# Pi-XMEGA.net
KiCad netlist of a schematic drawn in EAGLE
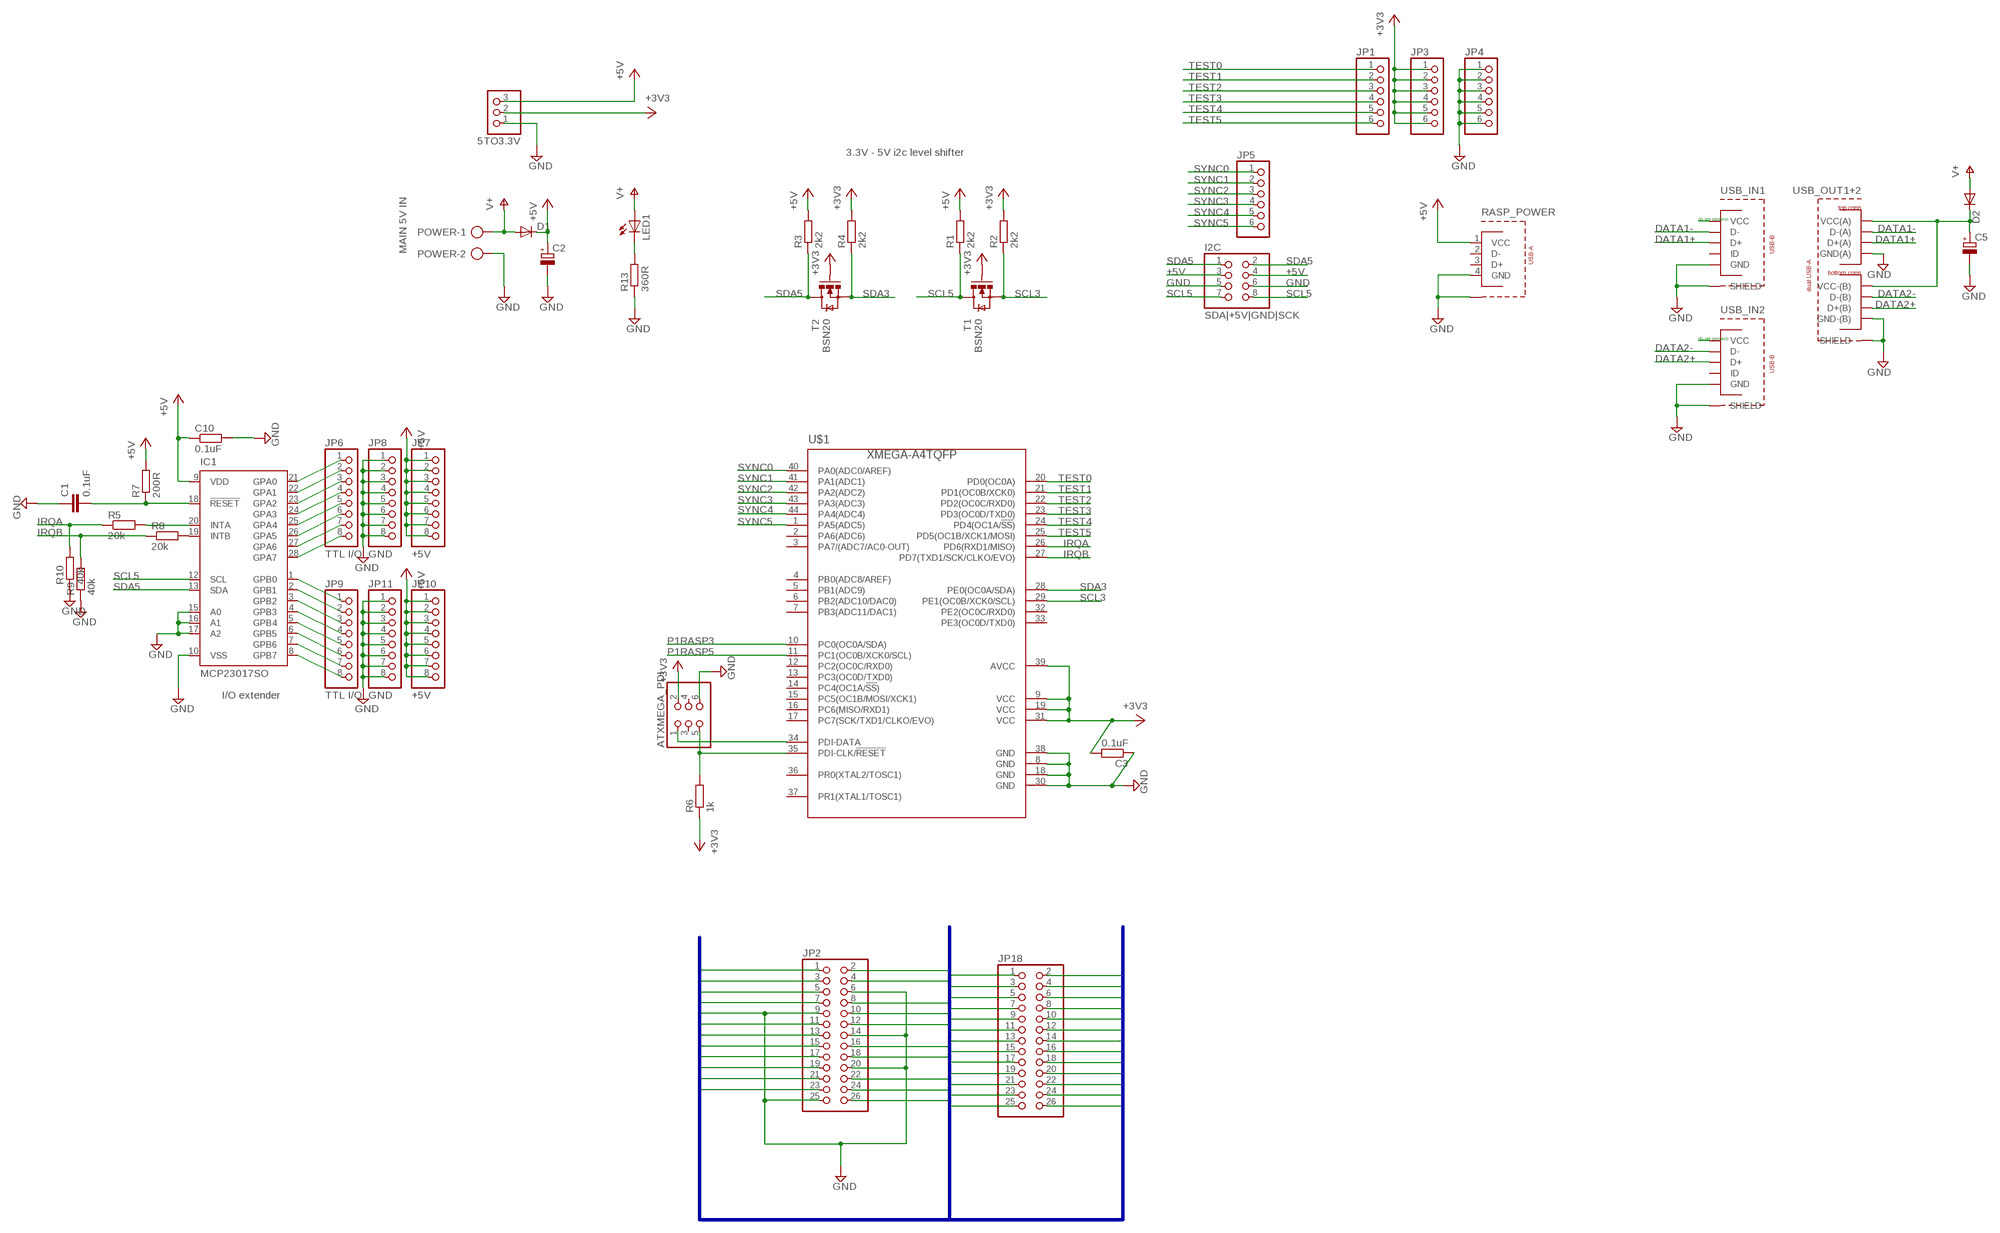
[diagram p0: schematic, sheet 1]

(export (version "E")
  (design (tool "Eeschema 10.0.6"))
  (components
    (comp (ref "5TO3.3V")
      (value "PINHD-1X3")
      (footprint "eagle-import:1X03")
      (libsource (lib "eagle-import") (part "PINHD-1X3"))
    )
    (comp (ref "ATXMEGA_PDI")
      (value "PINHD-2X03_2.54")
      (footprint "eagle-import:2X03")
      (libsource (lib "eagle-import") (part "PINHD-2X03_2.54"))
    )
    (comp (ref "C1")
      (value "0.1uF")
      (footprint "eagle-import:0805BIG")
      (libsource (lib "eagle-import") (part "CAPACITORC-0805BIG"))
    )
    (comp (ref "C2")
      (value "CPOL-EUE5-8.5")
      (footprint "eagle-import:E5-8,5")
      (libsource (lib "eagle-import") (part "CPOL-EUE5-8.5"))
    )
    (comp (ref "C3")
      (value "0.1uF")
      (footprint "eagle-import:0805BIG")
      (libsource (lib "eagle-import") (part "RESISTORR-0805BIG"))
    )
    (comp (ref "C5")
      (value "CPOL-EUE5-8.5")
      (footprint "eagle-import:E5-8,5")
      (libsource (lib "eagle-import") (part "CPOL-EUE5-8.5"))
    )
    (comp (ref "C10")
      (value "0.1uF")
      (footprint "eagle-import:0805BIG")
      (libsource (lib "eagle-import") (part "RESISTORR-0805BIG"))
    )
    (comp (ref "D1")
      (value "DIODE-C1702-05")
      (footprint "eagle-import:C1702-05")
      (libsource (lib "eagle-import") (part "DIODE-C1702-05"))
    )
    (comp (ref "D2")
      (value "DIODE-C1702-05")
      (footprint "eagle-import:C1702-05")
      (libsource (lib "eagle-import") (part "DIODE-C1702-05"))
    )
    (comp (ref "I2C")
      (value "SDA|+5V|GND|SCK")
      (footprint "eagle-import:2X04")
      (libsource (lib "eagle-import") (part "PINHD-2X04_2.54"))
    )
    (comp (ref "IC1")
      (value "MCP23017SO")
      (footprint "eagle-import:SO28W")
      (fields (field (name "MF") "MICROCHIP") (field (name "MPN") "MCP23017-E/SO"))
      (libsource (lib "eagle-import") (part "MCP23017SO"))
    )
    (comp (ref "JP1")
      (value "PINHD-1X06_2.54-S")
      (footprint "eagle-import:1X06-S")
      (libsource (lib "eagle-import") (part "PINHD-1X06_2.54-S"))
    )
    (comp (ref "JP2")
      (value "PINHD-2X13_2.54")
      (footprint "eagle-import:2X13")
      (libsource (lib "eagle-import") (part "PINHD-2X13_2.54"))
    )
    (comp (ref "JP3")
      (value "PINHD-1X06_2.54-S")
      (footprint "eagle-import:1X06-S")
      (libsource (lib "eagle-import") (part "PINHD-1X06_2.54-S"))
    )
    (comp (ref "JP4")
      (value "PINHD-1X06_2.54-S")
      (footprint "eagle-import:1X06-S")
      (libsource (lib "eagle-import") (part "PINHD-1X06_2.54-S"))
    )
    (comp (ref "JP5")
      (value "PINHD-1X06_2.54-S")
      (footprint "eagle-import:1X06-S")
      (libsource (lib "eagle-import") (part "PINHD-1X06_2.54-S"))
    )
    (comp (ref "JP6")
      (value "TTL I/O")
      (footprint "eagle-import:1X08-S")
      (libsource (lib "eagle-import") (part "PINHD-1X08_2.54-S"))
    )
    (comp (ref "JP7")
      (value "+5V")
      (footprint "eagle-import:1X08-S")
      (libsource (lib "eagle-import") (part "PINHD-1X08_2.54-S"))
    )
    (comp (ref "JP8")
      (value "GND")
      (footprint "eagle-import:1X08-S")
      (libsource (lib "eagle-import") (part "PINHD-1X08_2.54-S"))
    )
    (comp (ref "JP9")
      (value "TTL I/O")
      (footprint "eagle-import:1X08-S")
      (libsource (lib "eagle-import") (part "PINHD-1X08_2.54-S"))
    )
    (comp (ref "JP10")
      (value "+5V")
      (footprint "eagle-import:1X08-S")
      (libsource (lib "eagle-import") (part "PINHD-1X08_2.54-S"))
    )
    (comp (ref "JP11")
      (value "GND")
      (footprint "eagle-import:1X08-S")
      (libsource (lib "eagle-import") (part "PINHD-1X08_2.54-S"))
    )
    (comp (ref "JP18")
      (value "PINHD-2X13_2.54")
      (footprint "eagle-import:2X13")
      (libsource (lib "eagle-import") (part "PINHD-2X13_2.54"))
    )
    (comp (ref "LED1")
      (value "LED3MM")
      (footprint "eagle-import:LED3MM")
      (libsource (lib "eagle-import") (part "LED3MM"))
    )
    (comp (ref "POWER")
      (value "AK500/2")
      (footprint "eagle-import:AK500_2")
      (libsource (lib "eagle-import") (part "AK500/2"))
    )
    (comp (ref "R1")
      (value "2k2")
      (footprint "eagle-import:0805BIG")
      (libsource (lib "eagle-import") (part "RESISTORR-0805BIG"))
    )
    (comp (ref "R2")
      (value "2k2")
      (footprint "eagle-import:0805BIG")
      (libsource (lib "eagle-import") (part "RESISTORR-0805BIG"))
    )
    (comp (ref "R3")
      (value "2k2")
      (footprint "eagle-import:0805BIG")
      (libsource (lib "eagle-import") (part "MART2013_RESISTORR-0805BIG"))
    )
    (comp (ref "R4")
      (value "2k2")
      (footprint "eagle-import:0805BIG")
      (libsource (lib "eagle-import") (part "RESISTORR-0805BIG"))
    )
    (comp (ref "R5")
      (value "20k")
      (footprint "eagle-import:0805BIG")
      (libsource (lib "eagle-import") (part "RESISTORR-0805BIG"))
    )
    (comp (ref "R6")
      (value "1k")
      (footprint "eagle-import:0805BIG")
      (libsource (lib "eagle-import") (part "RESISTORR-0805BIG"))
    )
    (comp (ref "R7")
      (value "200R")
      (footprint "eagle-import:0805BIG")
      (libsource (lib "eagle-import") (part "RESISTORR-0805BIG"))
    )
    (comp (ref "R8")
      (value "20k")
      (footprint "eagle-import:0805BIG")
      (libsource (lib "eagle-import") (part "RESISTORR-0805BIG"))
    )
    (comp (ref "R9")
      (value "40k")
      (footprint "eagle-import:0805BIG")
      (libsource (lib "eagle-import") (part "RESISTORR-0805BIG"))
    )
    (comp (ref "R10")
      (value "40k")
      (footprint "eagle-import:0805BIG")
      (libsource (lib "eagle-import") (part "RESISTORR-0805BIG"))
    )
    (comp (ref "R13")
      (value "360R")
      (footprint "eagle-import:0805BIG")
      (libsource (lib "eagle-import") (part "RESISTORR-0805BIG"))
    )
    (comp (ref "RASP_POWER")
      (value "USB-A")
      (footprint "eagle-import:USB-A")
      (libsource (lib "eagle-import") (part "USB-A"))
    )
    (comp (ref "T1")
      (value "BSN20")
      (footprint "eagle-import:SOT23")
      (libsource (lib "eagle-import") (part "BSN20"))
    )
    (comp (ref "T2")
      (value "BSN20")
      (footprint "eagle-import:SOT23")
      (libsource (lib "eagle-import") (part "BSN20"))
    )
    (comp (ref "U$1")
      (value "XMEGA-A4TQFP")
      (footprint "eagle-import:TQFP44")
      (libsource (lib "eagle-import") (part "XMEGA-A4TQFP"))
    )
    (comp (ref "USB_IN1")
      (value "USB-B-MICRO")
      (footprint "eagle-import:USB-B-MICRO")
      (libsource (lib "eagle-import") (part "USB-B-MICRO"))
    )
    (comp (ref "USB_IN2")
      (value "USB-B-MICRO")
      (footprint "eagle-import:USB-B-MICRO")
      (libsource (lib "eagle-import") (part "USB-B-MICRO"))
    )
    (comp (ref "USB_OUT1+2")
      (value "DUAL-USB-A")
      (footprint "eagle-import:DUAL-USB-A")
      (libsource (lib "eagle-import") (part "DUAL-USB-A"))
    )
  )
  (nets
    (net (code "1") (name "+3V3") (class "Default")
      (node (ref "5TO3.3V") (pin "2") (pinfunction "2_2") (pintype "passive"))
      (node (ref "ATXMEGA_PDI") (pin "2") (pinfunction "2_2") (pintype "passive"))
      (node (ref "C3") (pin "2") (pinfunction "2_2") (pintype "passive"))
      (node (ref "JP3") (pin "1") (pinfunction "1_1") (pintype "passive"))
      (node (ref "JP3") (pin "2") (pinfunction "2_2") (pintype "passive"))
      (node (ref "JP3") (pin "3") (pinfunction "3_3") (pintype "passive"))
      (node (ref "JP3") (pin "4") (pinfunction "4_4") (pintype "passive"))
      (node (ref "JP3") (pin "5") (pinfunction "5_5") (pintype "passive"))
      (node (ref "JP3") (pin "6") (pinfunction "6_6") (pintype "passive"))
      (node (ref "R2") (pin "2") (pinfunction "2_2") (pintype "passive"))
      (node (ref "R4") (pin "2") (pinfunction "2_2") (pintype "passive"))
      (node (ref "R6") (pin "1") (pinfunction "1_1") (pintype "passive"))
      (node (ref "T1") (pin "1") (pinfunction "G_1") (pintype "passive"))
      (node (ref "T2") (pin "1") (pinfunction "G_1") (pintype "passive"))
      (node (ref "U$1") (pin "19") (pinfunction "VCC_19") (pintype "power_in"))
      (node (ref "U$1") (pin "31") (pinfunction "VCC_31") (pintype "power_in"))
      (node (ref "U$1") (pin "39") (pinfunction "AVCC_39") (pintype "power_in"))
      (node (ref "U$1") (pin "9") (pinfunction "VCC_9") (pintype "power_in"))
    )
    (net (code "2") (name "+5V") (class "Default")
      (node (ref "5TO3.3V") (pin "3") (pinfunction "3_3") (pintype "passive"))
      (node (ref "C10") (pin "1") (pinfunction "1_1") (pintype "passive"))
      (node (ref "C2") (pin "+") (pinfunction "+_+") (pintype "passive"))
      (node (ref "D1") (pin "C") (pinfunction "C_C") (pintype "passive"))
      (node (ref "I2C") (pin "3") (pinfunction "3_3") (pintype "passive"))
      (node (ref "I2C") (pin "4") (pinfunction "4_4") (pintype "passive"))
      (node (ref "IC1") (pin "9") (pinfunction "VDD_9") (pintype "power_in"))
      (node (ref "JP10") (pin "1") (pinfunction "1_1") (pintype "passive"))
      (node (ref "JP10") (pin "2") (pinfunction "2_2") (pintype "passive"))
      (node (ref "JP10") (pin "3") (pinfunction "3_3") (pintype "passive"))
      (node (ref "JP10") (pin "4") (pinfunction "4_4") (pintype "passive"))
      (node (ref "JP10") (pin "5") (pinfunction "5_5") (pintype "passive"))
      (node (ref "JP10") (pin "6") (pinfunction "6_6") (pintype "passive"))
      (node (ref "JP10") (pin "7") (pinfunction "7_7") (pintype "passive"))
      (node (ref "JP10") (pin "8") (pinfunction "8_8") (pintype "passive"))
      (node (ref "JP7") (pin "1") (pinfunction "1_1") (pintype "passive"))
      (node (ref "JP7") (pin "2") (pinfunction "2_2") (pintype "passive"))
      (node (ref "JP7") (pin "3") (pinfunction "3_3") (pintype "passive"))
      (node (ref "JP7") (pin "4") (pinfunction "4_4") (pintype "passive"))
      (node (ref "JP7") (pin "5") (pinfunction "5_5") (pintype "passive"))
      (node (ref "JP7") (pin "6") (pinfunction "6_6") (pintype "passive"))
      (node (ref "JP7") (pin "7") (pinfunction "7_7") (pintype "passive"))
      (node (ref "JP7") (pin "8") (pinfunction "8_8") (pintype "passive"))
      (node (ref "R1") (pin "2") (pinfunction "2_2") (pintype "passive"))
      (node (ref "R3") (pin "2") (pinfunction "2_2") (pintype "passive"))
      (node (ref "R7") (pin "2") (pinfunction "2_2") (pintype "passive"))
      (node (ref "RASP_POWER") (pin "1") (pinfunction "VCC_1") (pintype "power_in"))
    )
    (net (code "3") (name "/DATA1+") (class "Default")
      (node (ref "USB_IN1") (pin "3") (pinfunction "D+_3") (pintype "bidirectional"))
      (node (ref "USB_OUT1+2") (pin "3") (pinfunction "D+(A)_3") (pintype "bidirectional"))
    )
    (net (code "4") (name "/DATA1-") (class "Default")
      (node (ref "USB_IN1") (pin "2") (pinfunction "D-_2") (pintype "bidirectional"))
      (node (ref "USB_OUT1+2") (pin "2") (pinfunction "D-(A)_2") (pintype "bidirectional"))
    )
    (net (code "5") (name "/DATA2+") (class "Default")
      (node (ref "USB_IN2") (pin "3") (pinfunction "D+_3") (pintype "bidirectional"))
      (node (ref "USB_OUT1+2") (pin "7") (pinfunction "D+(B)_7") (pintype "bidirectional"))
    )
    (net (code "6") (name "/DATA2-") (class "Default")
      (node (ref "USB_IN2") (pin "2") (pinfunction "D-_2") (pintype "bidirectional"))
      (node (ref "USB_OUT1+2") (pin "6") (pinfunction "D-(B)_6") (pintype "bidirectional"))
    )
    (net (code "7") (name "/IRQA") (class "Default")
      (node (ref "R10") (pin "2") (pinfunction "2_2") (pintype "passive"))
      (node (ref "R5") (pin "1") (pinfunction "1_1") (pintype "passive"))
      (node (ref "U$1") (pin "26") (pinfunction "PD6(RXD1/MISO)_26") (pintype "bidirectional"))
    )
    (net (code "8") (name "/IRQB") (class "Default")
      (node (ref "R8") (pin "1") (pinfunction "1_1") (pintype "passive"))
      (node (ref "R9") (pin "2") (pinfunction "2_2") (pintype "passive"))
      (node (ref "U$1") (pin "27") (pinfunction "PD7(TXD1/SCK/CLKO/EVO)_27") (pintype "bidirectional"))
    )
    (net (code "9") (name "/P1RASP1") (class "Default")
      (node (ref "JP18") (pin "1") (pinfunction "1_1") (pintype "passive"))
      (node (ref "JP2") (pin "1") (pinfunction "1_1") (pintype "passive"))
    )
    (net (code "10") (name "/P1RASP2") (class "Default")
      (node (ref "JP18") (pin "2") (pinfunction "2_2") (pintype "passive"))
      (node (ref "JP2") (pin "2") (pinfunction "2_2") (pintype "passive"))
    )
    (net (code "11") (name "/P1RASP3") (class "Default")
      (node (ref "JP18") (pin "3") (pinfunction "3_3") (pintype "passive"))
      (node (ref "JP2") (pin "3") (pinfunction "3_3") (pintype "passive"))
      (node (ref "U$1") (pin "10") (pinfunction "PC0(OC0A/SDA)_10") (pintype "bidirectional"))
    )
    (net (code "12") (name "/P1RASP4") (class "Default")
      (node (ref "JP18") (pin "4") (pinfunction "4_4") (pintype "passive"))
      (node (ref "JP2") (pin "4") (pinfunction "4_4") (pintype "passive"))
    )
    (net (code "13") (name "/P1RASP5") (class "Default")
      (node (ref "JP18") (pin "5") (pinfunction "5_5") (pintype "passive"))
      (node (ref "JP2") (pin "5") (pinfunction "5_5") (pintype "passive"))
      (node (ref "U$1") (pin "11") (pinfunction "PC1(OC0B/XCK0/SCL)_11") (pintype "bidirectional"))
    )
    (net (code "14") (name "/P1RASP7") (class "Default")
      (node (ref "JP18") (pin "7") (pinfunction "7_7") (pintype "passive"))
      (node (ref "JP2") (pin "7") (pinfunction "7_7") (pintype "passive"))
    )
    (net (code "15") (name "/P1RASP8") (class "Default")
      (node (ref "JP18") (pin "8") (pinfunction "8_8") (pintype "passive"))
      (node (ref "JP2") (pin "8") (pinfunction "8_8") (pintype "passive"))
    )
    (net (code "16") (name "/P1RASP10") (class "Default")
      (node (ref "JP18") (pin "10") (pinfunction "10_10") (pintype "passive"))
      (node (ref "JP2") (pin "10") (pinfunction "10_10") (pintype "passive"))
    )
    (net (code "17") (name "/P1RASP11") (class "Default")
      (node (ref "JP18") (pin "11") (pinfunction "11_11") (pintype "passive"))
      (node (ref "JP2") (pin "11") (pinfunction "11_11") (pintype "passive"))
    )
    (net (code "18") (name "/P1RASP12") (class "Default")
      (node (ref "JP18") (pin "12") (pinfunction "12_12") (pintype "passive"))
      (node (ref "JP2") (pin "12") (pinfunction "12_12") (pintype "passive"))
    )
    (net (code "19") (name "/P1RASP13") (class "Default")
      (node (ref "JP18") (pin "13") (pinfunction "13_13") (pintype "passive"))
      (node (ref "JP2") (pin "13") (pinfunction "13_13") (pintype "passive"))
    )
    (net (code "20") (name "/P1RASP15") (class "Default")
      (node (ref "JP18") (pin "15") (pinfunction "15_15") (pintype "passive"))
      (node (ref "JP2") (pin "15") (pinfunction "15_15") (pintype "passive"))
    )
    (net (code "21") (name "/P1RASP16") (class "Default")
      (node (ref "JP18") (pin "16") (pinfunction "16_16") (pintype "passive"))
      (node (ref "JP2") (pin "16") (pinfunction "16_16") (pintype "passive"))
    )
    (net (code "22") (name "/P1RASP17") (class "Default")
      (node (ref "JP18") (pin "17") (pinfunction "17_17") (pintype "passive"))
      (node (ref "JP2") (pin "17") (pinfunction "17_17") (pintype "passive"))
    )
    (net (code "23") (name "/P1RASP18") (class "Default")
      (node (ref "JP18") (pin "18") (pinfunction "18_18") (pintype "passive"))
      (node (ref "JP2") (pin "18") (pinfunction "18_18") (pintype "passive"))
    )
    (net (code "24") (name "/P1RASP19") (class "Default")
      (node (ref "JP18") (pin "19") (pinfunction "19_19") (pintype "passive"))
      (node (ref "JP2") (pin "19") (pinfunction "19_19") (pintype "passive"))
    )
    (net (code "25") (name "/P1RASP21") (class "Default")
      (node (ref "JP18") (pin "21") (pinfunction "21_21") (pintype "passive"))
      (node (ref "JP2") (pin "21") (pinfunction "21_21") (pintype "passive"))
    )
    (net (code "26") (name "/P1RASP22") (class "Default")
      (node (ref "JP18") (pin "22") (pinfunction "22_22") (pintype "passive"))
      (node (ref "JP2") (pin "22") (pinfunction "22_22") (pintype "passive"))
    )
    (net (code "27") (name "/P1RASP23") (class "Default")
      (node (ref "JP18") (pin "23") (pinfunction "23_23") (pintype "passive"))
      (node (ref "JP2") (pin "23") (pinfunction "23_23") (pintype "passive"))
    )
    (net (code "28") (name "/P1RASP24") (class "Default")
      (node (ref "JP18") (pin "24") (pinfunction "24_24") (pintype "passive"))
      (node (ref "JP2") (pin "24") (pinfunction "24_24") (pintype "passive"))
    )
    (net (code "29") (name "/P1RASP26") (class "Default")
      (node (ref "JP18") (pin "26") (pinfunction "26_26") (pintype "passive"))
      (node (ref "JP2") (pin "26") (pinfunction "26_26") (pintype "passive"))
    )
    (net (code "30") (name "/SCL3") (class "Default")
      (node (ref "R2") (pin "1") (pinfunction "1_1") (pintype "passive"))
      (node (ref "T1") (pin "2") (pinfunction "S_2") (pintype "passive"))
      (node (ref "U$1") (pin "29") (pinfunction "PE1(OC0B/XCK0/SCL)_29") (pintype "bidirectional"))
    )
    (net (code "31") (name "/SCL5") (class "Default")
      (node (ref "I2C") (pin "7") (pinfunction "7_7") (pintype "passive"))
      (node (ref "I2C") (pin "8") (pinfunction "8_8") (pintype "passive"))
      (node (ref "IC1") (pin "12") (pinfunction "SCL_12") (pintype "input"))
      (node (ref "R1") (pin "1") (pinfunction "1_1") (pintype "passive"))
      (node (ref "T1") (pin "3") (pinfunction "D_3") (pintype "passive"))
    )
    (net (code "32") (name "/SDA3") (class "Default")
      (node (ref "R4") (pin "1") (pinfunction "1_1") (pintype "passive"))
      (node (ref "T2") (pin "2") (pinfunction "S_2") (pintype "passive"))
      (node (ref "U$1") (pin "28") (pinfunction "PE0(OC0A/SDA)_28") (pintype "bidirectional"))
    )
    (net (code "33") (name "/SDA5") (class "Default")
      (node (ref "I2C") (pin "1") (pinfunction "1_1") (pintype "passive"))
      (node (ref "I2C") (pin "2") (pinfunction "2_2") (pintype "passive"))
      (node (ref "IC1") (pin "13") (pinfunction "SDA_13") (pintype "bidirectional"))
      (node (ref "R3") (pin "1") (pinfunction "1_1") (pintype "passive"))
      (node (ref "T2") (pin "3") (pinfunction "D_3") (pintype "passive"))
    )
    (net (code "34") (name "/SYNC0") (class "Default")
      (node (ref "JP5") (pin "1") (pinfunction "1_1") (pintype "passive"))
      (node (ref "U$1") (pin "40") (pinfunction "PA0(ADC0/AREF)_40") (pintype "bidirectional"))
    )
    (net (code "35") (name "/SYNC1") (class "Default")
      (node (ref "JP5") (pin "2") (pinfunction "2_2") (pintype "passive"))
      (node (ref "U$1") (pin "41") (pinfunction "PA1(ADC1)_41") (pintype "bidirectional"))
    )
    (net (code "36") (name "/SYNC2") (class "Default")
      (node (ref "JP5") (pin "3") (pinfunction "3_3") (pintype "passive"))
      (node (ref "U$1") (pin "42") (pinfunction "PA2(ADC2)_42") (pintype "bidirectional"))
    )
    (net (code "37") (name "/SYNC3") (class "Default")
      (node (ref "JP5") (pin "4") (pinfunction "4_4") (pintype "passive"))
      (node (ref "U$1") (pin "43") (pinfunction "PA3(ADC3)_43") (pintype "bidirectional"))
    )
    (net (code "38") (name "/SYNC4") (class "Default")
      (node (ref "JP5") (pin "5") (pinfunction "5_5") (pintype "passive"))
      (node (ref "U$1") (pin "44") (pinfunction "PA4(ADC4)_44") (pintype "bidirectional"))
    )
    (net (code "39") (name "/SYNC5") (class "Default")
      (node (ref "JP5") (pin "6") (pinfunction "6_6") (pintype "passive"))
      (node (ref "U$1") (pin "1") (pinfunction "PA5(ADC5)_1") (pintype "bidirectional"))
    )
    (net (code "40") (name "/TEST0") (class "Default")
      (node (ref "JP1") (pin "1") (pinfunction "1_1") (pintype "passive"))
      (node (ref "U$1") (pin "20") (pinfunction "PD0(OC0A)_20") (pintype "bidirectional"))
    )
    (net (code "41") (name "/TEST1") (class "Default")
      (node (ref "JP1") (pin "2") (pinfunction "2_2") (pintype "passive"))
      (node (ref "U$1") (pin "21") (pinfunction "PD1(OC0B/XCK0)_21") (pintype "bidirectional"))
    )
    (net (code "42") (name "/TEST2") (class "Default")
      (node (ref "JP1") (pin "3") (pinfunction "3_3") (pintype "passive"))
      (node (ref "U$1") (pin "22") (pinfunction "PD2(OC0C/RXD0)_22") (pintype "bidirectional"))
    )
    (net (code "43") (name "/TEST3") (class "Default")
      (node (ref "JP1") (pin "4") (pinfunction "4_4") (pintype "passive"))
      (node (ref "U$1") (pin "23") (pinfunction "PD3(OC0D/TXD0)_23") (pintype "bidirectional"))
    )
    (net (code "44") (name "/TEST4") (class "Default")
      (node (ref "JP1") (pin "5") (pinfunction "5_5") (pintype "passive"))
      (node (ref "U$1") (pin "24") (pinfunction "PD4(OC1A/~{SS})_24") (pintype "bidirectional"))
    )
    (net (code "45") (name "/TEST5") (class "Default")
      (node (ref "JP1") (pin "6") (pinfunction "6_6") (pintype "passive"))
      (node (ref "U$1") (pin "25") (pinfunction "PD5(OC1B/XCK1/MOSI)_25") (pintype "bidirectional"))
    )
    (net (code "46") (name "GND") (class "Default")
      (node (ref "5TO3.3V") (pin "1") (pinfunction "1_1") (pintype "passive"))
      (node (ref "ATXMEGA_PDI") (pin "6") (pinfunction "6_6") (pintype "passive"))
      (node (ref "C1") (pin "1") (pinfunction "1_1") (pintype "passive"))
      (node (ref "C10") (pin "2") (pinfunction "2_2") (pintype "passive"))
      (node (ref "C2") (pin "-") (pinfunction "-_-") (pintype "passive"))
      (node (ref "C3") (pin "1") (pinfunction "1_1") (pintype "passive"))
      (node (ref "C5") (pin "-") (pinfunction "-_-") (pintype "passive"))
      (node (ref "I2C") (pin "5") (pinfunction "5_5") (pintype "passive"))
      (node (ref "I2C") (pin "6") (pinfunction "6_6") (pintype "passive"))
      (node (ref "IC1") (pin "10") (pinfunction "VSS_10") (pintype "power_in"))
      (node (ref "IC1") (pin "15") (pinfunction "A0_15") (pintype "input"))
      (node (ref "IC1") (pin "16") (pinfunction "A1_16") (pintype "input"))
      (node (ref "IC1") (pin "17") (pinfunction "A2_17") (pintype "input"))
      (node (ref "JP11") (pin "1") (pinfunction "1_1") (pintype "passive"))
      (node (ref "JP11") (pin "2") (pinfunction "2_2") (pintype "passive"))
      (node (ref "JP11") (pin "3") (pinfunction "3_3") (pintype "passive"))
      (node (ref "JP11") (pin "4") (pinfunction "4_4") (pintype "passive"))
      (node (ref "JP11") (pin "5") (pinfunction "5_5") (pintype "passive"))
      (node (ref "JP11") (pin "6") (pinfunction "6_6") (pintype "passive"))
      (node (ref "JP11") (pin "7") (pinfunction "7_7") (pintype "passive"))
      (node (ref "JP11") (pin "8") (pinfunction "8_8") (pintype "passive"))
      (node (ref "JP18") (pin "14") (pinfunction "14_14") (pintype "passive"))
      (node (ref "JP18") (pin "20") (pinfunction "20_20") (pintype "passive"))
      (node (ref "JP18") (pin "25") (pinfunction "25_25") (pintype "passive"))
      (node (ref "JP18") (pin "6") (pinfunction "6_6") (pintype "passive"))
      (node (ref "JP18") (pin "9") (pinfunction "9_9") (pintype "passive"))
      (node (ref "JP2") (pin "14") (pinfunction "14_14") (pintype "passive"))
      (node (ref "JP2") (pin "20") (pinfunction "20_20") (pintype "passive"))
      (node (ref "JP2") (pin "25") (pinfunction "25_25") (pintype "passive"))
      (node (ref "JP2") (pin "6") (pinfunction "6_6") (pintype "passive"))
      (node (ref "JP2") (pin "9") (pinfunction "9_9") (pintype "passive"))
      (node (ref "JP4") (pin "1") (pinfunction "1_1") (pintype "passive"))
      (node (ref "JP4") (pin "2") (pinfunction "2_2") (pintype "passive"))
      (node (ref "JP4") (pin "3") (pinfunction "3_3") (pintype "passive"))
      (node (ref "JP4") (pin "4") (pinfunction "4_4") (pintype "passive"))
      (node (ref "JP4") (pin "5") (pinfunction "5_5") (pintype "passive"))
      (node (ref "JP4") (pin "6") (pinfunction "6_6") (pintype "passive"))
      (node (ref "JP8") (pin "1") (pinfunction "1_1") (pintype "passive"))
      (node (ref "JP8") (pin "2") (pinfunction "2_2") (pintype "passive"))
      (node (ref "JP8") (pin "3") (pinfunction "3_3") (pintype "passive"))
      (node (ref "JP8") (pin "4") (pinfunction "4_4") (pintype "passive"))
      (node (ref "JP8") (pin "5") (pinfunction "5_5") (pintype "passive"))
      (node (ref "JP8") (pin "6") (pinfunction "6_6") (pintype "passive"))
      (node (ref "JP8") (pin "7") (pinfunction "7_7") (pintype "passive"))
      (node (ref "JP8") (pin "8") (pinfunction "8_8") (pintype "passive"))
      (node (ref "POWER") (pin "2") (pinfunction "KL_2") (pintype "passive"))
      (node (ref "R10") (pin "1") (pinfunction "1_1") (pintype "passive"))
      (node (ref "R13") (pin "1") (pinfunction "1_1") (pintype "passive"))
      (node (ref "R9") (pin "1") (pinfunction "1_1") (pintype "passive"))
      (node (ref "RASP_POWER") (pin "4") (pinfunction "GND_4") (pintype "power_in"))
      (node (ref "RASP_POWER") (pin "S1") (pinfunction "SHIELD_S1") (pintype "power_in"))
      (node (ref "RASP_POWER") (pin "S2") (pinfunction "SHIELD_S2") (pintype "power_in"))
      (node (ref "U$1") (pin "18") (pinfunction "GND_18") (pintype "power_in"))
      (node (ref "U$1") (pin "30") (pinfunction "GND_30") (pintype "power_in"))
      (node (ref "U$1") (pin "38") (pinfunction "GND_38") (pintype "power_in"))
      (node (ref "U$1") (pin "8") (pinfunction "GND_8") (pintype "power_in"))
      (node (ref "USB_IN1") (pin "5") (pinfunction "GND_5") (pintype "power_in"))
      (node (ref "USB_IN1") (pin "S1") (pinfunction "SHIELD_S1") (pintype "power_in"))
      (node (ref "USB_IN1") (pin "S2") (pinfunction "SHIELD_S2") (pintype "power_in"))
      (node (ref "USB_IN2") (pin "5") (pinfunction "GND_5") (pintype "power_in"))
      (node (ref "USB_IN2") (pin "S1") (pinfunction "SHIELD_S1") (pintype "power_in"))
      (node (ref "USB_IN2") (pin "S2") (pinfunction "SHIELD_S2") (pintype "power_in"))
      (node (ref "USB_OUT1+2") (pin "4") (pinfunction "GND(A)_4") (pintype "power_in"))
      (node (ref "USB_OUT1+2") (pin "8") (pinfunction "GND-(B)_8") (pintype "power_in"))
      (node (ref "USB_OUT1+2") (pin "S1") (pinfunction "SHIELD_S1") (pintype "power_in"))
      (node (ref "USB_OUT1+2") (pin "S2") (pinfunction "SHIELD_S2") (pintype "power_in"))
      (node (ref "USB_OUT1+2") (pin "S3") (pinfunction "SHIELD_S3") (pintype "power_in"))
      (node (ref "USB_OUT1+2") (pin "S4") (pinfunction "SHIELD_S4") (pintype "power_in"))
    )
    (net (code "47") (name "Net-(IC1-GPA0)") (class "Default")
      (node (ref "IC1") (pin "21") (pinfunction "GPA0_21") (pintype "bidirectional"))
      (node (ref "JP6") (pin "1") (pinfunction "1_1") (pintype "passive"))
    )
    (net (code "48") (name "Net-(IC1-GPA1)") (class "Default")
      (node (ref "IC1") (pin "22") (pinfunction "GPA1_22") (pintype "bidirectional"))
      (node (ref "JP6") (pin "2") (pinfunction "2_2") (pintype "passive"))
    )
    (net (code "49") (name "Net-(IC1-GPA2)") (class "Default")
      (node (ref "IC1") (pin "23") (pinfunction "GPA2_23") (pintype "bidirectional"))
      (node (ref "JP6") (pin "3") (pinfunction "3_3") (pintype "passive"))
    )
    (net (code "50") (name "Net-(IC1-GPA3)") (class "Default")
      (node (ref "IC1") (pin "24") (pinfunction "GPA3_24") (pintype "bidirectional"))
      (node (ref "JP6") (pin "4") (pinfunction "4_4") (pintype "passive"))
    )
    (net (code "51") (name "Net-(IC1-GPA4)") (class "Default")
      (node (ref "IC1") (pin "25") (pinfunction "GPA4_25") (pintype "bidirectional"))
      (node (ref "JP6") (pin "5") (pinfunction "5_5") (pintype "passive"))
    )
    (net (code "52") (name "Net-(IC1-GPA5)") (class "Default")
      (node (ref "IC1") (pin "26") (pinfunction "GPA5_26") (pintype "bidirectional"))
      (node (ref "JP6") (pin "6") (pinfunction "6_6") (pintype "passive"))
    )
    (net (code "53") (name "Net-(IC1-GPA6)") (class "Default")
      (node (ref "IC1") (pin "27") (pinfunction "GPA6_27") (pintype "bidirectional"))
      (node (ref "JP6") (pin "7") (pinfunction "7_7") (pintype "passive"))
    )
    (net (code "54") (name "Net-(IC1-GPA7)") (class "Default")
      (node (ref "IC1") (pin "28") (pinfunction "GPA7_28") (pintype "bidirectional"))
      (node (ref "JP6") (pin "8") (pinfunction "8_8") (pintype "passive"))
    )
    (net (code "55") (name "Net-(IC1-GPB0)") (class "Default")
      (node (ref "IC1") (pin "1") (pinfunction "GPB0_1") (pintype "bidirectional"))
      (node (ref "JP9") (pin "1") (pinfunction "1_1") (pintype "passive"))
    )
    (net (code "56") (name "Net-(IC1-GPB1)") (class "Default")
      (node (ref "IC1") (pin "2") (pinfunction "GPB1_2") (pintype "bidirectional"))
      (node (ref "JP9") (pin "2") (pinfunction "2_2") (pintype "passive"))
    )
    (net (code "57") (name "Net-(IC1-GPB2)") (class "Default")
      (node (ref "IC1") (pin "3") (pinfunction "GPB2_3") (pintype "bidirectional"))
      (node (ref "JP9") (pin "3") (pinfunction "3_3") (pintype "passive"))
    )
    (net (code "58") (name "Net-(IC1-GPB3)") (class "Default")
      (node (ref "IC1") (pin "4") (pinfunction "GPB3_4") (pintype "bidirectional"))
      (node (ref "JP9") (pin "4") (pinfunction "4_4") (pintype "passive"))
    )
    (net (code "59") (name "Net-(IC1-GPB4)") (class "Default")
      (node (ref "IC1") (pin "5") (pinfunction "GPB4_5") (pintype "bidirectional"))
      (node (ref "JP9") (pin "5") (pinfunction "5_5") (pintype "passive"))
    )
    (net (code "60") (name "Net-(IC1-GPB5)") (class "Default")
      (node (ref "IC1") (pin "6") (pinfunction "GPB5_6") (pintype "bidirectional"))
      (node (ref "JP9") (pin "6") (pinfunction "6_6") (pintype "passive"))
    )
    (net (code "61") (name "Net-(IC1-GPB6)") (class "Default")
      (node (ref "IC1") (pin "7") (pinfunction "GPB6_7") (pintype "bidirectional"))
      (node (ref "JP9") (pin "7") (pinfunction "7_7") (pintype "passive"))
    )
    (net (code "62") (name "Net-(IC1-GPB7)") (class "Default")
      (node (ref "IC1") (pin "8") (pinfunction "GPB7_8") (pintype "bidirectional"))
      (node (ref "JP9") (pin "8") (pinfunction "8_8") (pintype "passive"))
    )
    (net (code "63") (name "Net-(IC1-INTA)") (class "Default")
      (node (ref "IC1") (pin "20") (pinfunction "INTA_20") (pintype "output"))
      (node (ref "R5") (pin "2") (pinfunction "2_2") (pintype "passive"))
    )
    (net (code "64") (name "Net-(IC1-INTB)") (class "Default")
      (node (ref "IC1") (pin "19") (pinfunction "INTB_19") (pintype "output"))
      (node (ref "R8") (pin "2") (pinfunction "2_2") (pintype "passive"))
    )
    (net (code "65") (name "Net-(IC1-~{RESET})") (class "Default")
      (node (ref "C1") (pin "2") (pinfunction "2_2") (pintype "passive"))
      (node (ref "IC1") (pin "18") (pinfunction "~{RESET}_18") (pintype "input"))
      (node (ref "R7") (pin "1") (pinfunction "1_1") (pintype "passive"))
    )
    (net (code "66") (name "Net-(LED1-C)") (class "Default")
      (node (ref "LED1") (pin "K") (pinfunction "C_K") (pintype "passive"))
      (node (ref "R13") (pin "2") (pinfunction "2_2") (pintype "passive"))
    )
    (net (code "67") (name "Net-(U$1-PDI-CLK{slash}~{RESET})") (class "Default")
      (node (ref "ATXMEGA_PDI") (pin "5") (pinfunction "5_5") (pintype "passive"))
      (node (ref "R6") (pin "2") (pinfunction "2_2") (pintype "passive"))
      (node (ref "U$1") (pin "35") (pinfunction "PDI-CLK/~{RESET}_35") (pintype "input"))
    )
    (net (code "68") (name "Net-(U$1-PDI-DATA)") (class "Default")
      (node (ref "ATXMEGA_PDI") (pin "1") (pinfunction "1_1") (pintype "passive"))
      (node (ref "U$1") (pin "34") (pinfunction "PDI-DATA_34") (pintype "bidirectional"))
    )
    (net (code "69") (name "Net-(USB_OUT1+2-VCC(A))") (class "Default")
      (node (ref "C5") (pin "+") (pinfunction "+_+") (pintype "passive"))
      (node (ref "D2") (pin "C") (pinfunction "C_C") (pintype "passive"))
      (node (ref "USB_OUT1+2") (pin "1") (pinfunction "VCC(A)_1") (pintype "power_in"))
      (node (ref "USB_OUT1+2") (pin "5") (pinfunction "VCC-(B)_5") (pintype "power_in"))
    )
    (net (code "70") (name "V+") (class "Default")
      (node (ref "D1") (pin "A") (pinfunction "A_A") (pintype "passive"))
      (node (ref "D2") (pin "A") (pinfunction "A_A") (pintype "passive"))
      (node (ref "LED1") (pin "A") (pinfunction "A_A") (pintype "passive"))
      (node (ref "POWER") (pin "1") (pinfunction "KL_1") (pintype "passive"))
    )
    (net (code "71") (name "unconnected-(ATXMEGA_PDI-Pad3)") (class "Default")
      (node (ref "ATXMEGA_PDI") (pin "3") (pinfunction "3_3") (pintype "passive"))
    )
    (net (code "72") (name "unconnected-(ATXMEGA_PDI-Pad4)") (class "Default")
      (node (ref "ATXMEGA_PDI") (pin "4") (pinfunction "4_4") (pintype "passive"))
    )
    (net (code "73") (name "unconnected-(RASP_POWER-D+-Pad3)") (class "Default")
      (node (ref "RASP_POWER") (pin "3") (pinfunction "D+_3") (pintype "bidirectional"))
    )
    (net (code "74") (name "unconnected-(RASP_POWER-D--Pad2)") (class "Default")
      (node (ref "RASP_POWER") (pin "2") (pinfunction "D-_2") (pintype "bidirectional"))
    )
    (net (code "75") (name "unconnected-(U$1-PA6(ADC6)-Pad2)") (class "Default")
      (node (ref "U$1") (pin "2") (pinfunction "PA6(ADC6)_2") (pintype "bidirectional"))
    )
    (net (code "76") (name "unconnected-(U$1-PA7{slash}(ADC7{slash}AC0-OUT)-Pad3)") (class "Default")
      (node (ref "U$1") (pin "3") (pinfunction "PA7/(ADC7/AC0-OUT)_3") (pintype "bidirectional"))
    )
    (net (code "77") (name "unconnected-(U$1-PB0(ADC8{slash}AREF)-Pad4)") (class "Default")
      (node (ref "U$1") (pin "4") (pinfunction "PB0(ADC8/AREF)_4") (pintype "bidirectional"))
    )
    (net (code "78") (name "unconnected-(U$1-PB1(ADC9)-Pad5)") (class "Default")
      (node (ref "U$1") (pin "5") (pinfunction "PB1(ADC9)_5") (pintype "bidirectional"))
    )
    (net (code "79") (name "unconnected-(U$1-PB2(ADC10{slash}DAC0)-Pad6)") (class "Default")
      (node (ref "U$1") (pin "6") (pinfunction "PB2(ADC10/DAC0)_6") (pintype "bidirectional"))
    )
    (net (code "80") (name "unconnected-(U$1-PB3(ADC11{slash}DAC1)-Pad7)") (class "Default")
      (node (ref "U$1") (pin "7") (pinfunction "PB3(ADC11/DAC1)_7") (pintype "bidirectional"))
    )
    (net (code "81") (name "unconnected-(U$1-PC2(OC0C{slash}RXD0)-Pad12)") (class "Default")
      (node (ref "U$1") (pin "12") (pinfunction "PC2(OC0C/RXD0)_12") (pintype "bidirectional"))
    )
    (net (code "82") (name "unconnected-(U$1-PC3(OC0D{slash}TXD0)-Pad13)") (class "Default")
      (node (ref "U$1") (pin "13") (pinfunction "PC3(OC0D/TXD0)_13") (pintype "bidirectional"))
    )
    (net (code "83") (name "unconnected-(U$1-PC4(OC1A{slash}~{SS})-Pad14)") (class "Default")
      (node (ref "U$1") (pin "14") (pinfunction "PC4(OC1A/~{SS})_14") (pintype "bidirectional"))
    )
    (net (code "84") (name "unconnected-(U$1-PC5(OC1B{slash}MOSI{slash}XCK1)-Pad15)") (class "Default")
      (node (ref "U$1") (pin "15") (pinfunction "PC5(OC1B/MOSI/XCK1)_15") (pintype "bidirectional"))
    )
    (net (code "85") (name "unconnected-(U$1-PC6(MISO{slash}RXD1)-Pad16)") (class "Default")
      (node (ref "U$1") (pin "16") (pinfunction "PC6(MISO/RXD1)_16") (pintype "bidirectional"))
    )
    (net (code "86") (name "unconnected-(U$1-PC7(SCK{slash}TXD1{slash}CLKO{slash}EVO)-Pad17)") (class "Default")
      (node (ref "U$1") (pin "17") (pinfunction "PC7(SCK/TXD1/CLKO/EVO)_17") (pintype "bidirectional"))
    )
    (net (code "87") (name "unconnected-(U$1-PE2(OC0C{slash}RXD0)-Pad32)") (class "Default")
      (node (ref "U$1") (pin "32") (pinfunction "PE2(OC0C/RXD0)_32") (pintype "bidirectional"))
    )
    (net (code "88") (name "unconnected-(U$1-PE3(OC0D{slash}TXD0)-Pad33)") (class "Default")
      (node (ref "U$1") (pin "33") (pinfunction "PE3(OC0D/TXD0)_33") (pintype "bidirectional"))
    )
    (net (code "89") (name "unconnected-(U$1-PR0(XTAL2{slash}TOSC1)-Pad36)") (class "Default")
      (node (ref "U$1") (pin "36") (pinfunction "PR0(XTAL2/TOSC1)_36") (pintype "bidirectional"))
    )
    (net (code "90") (name "unconnected-(U$1-PR1(XTAL1{slash}TOSC1)-Pad37)") (class "Default")
      (node (ref "U$1") (pin "37") (pinfunction "PR1(XTAL1/TOSC1)_37") (pintype "bidirectional"))
    )
    (net (code "91") (name "unconnected-(USB_IN1-ID-Pad4)") (class "Default")
      (node (ref "USB_IN1") (pin "4") (pinfunction "ID_4") (pintype "bidirectional"))
    )
    (net (code "92") (name "unconnected-(USB_IN1-VCC-Pad1)") (class "Default")
      (node (ref "USB_IN1") (pin "1") (pinfunction "VCC_1") (pintype "power_in"))
    )
    (net (code "93") (name "unconnected-(USB_IN2-ID-Pad4)") (class "Default")
      (node (ref "USB_IN2") (pin "4") (pinfunction "ID_4") (pintype "bidirectional"))
    )
    (net (code "94") (name "unconnected-(USB_IN2-VCC-Pad1)") (class "Default")
      (node (ref "USB_IN2") (pin "1") (pinfunction "VCC_1") (pintype "power_in"))
    )
  )
)
